# HomemadeHardware_Intro.net
KiCad netlist of a schematic drawn in EAGLE
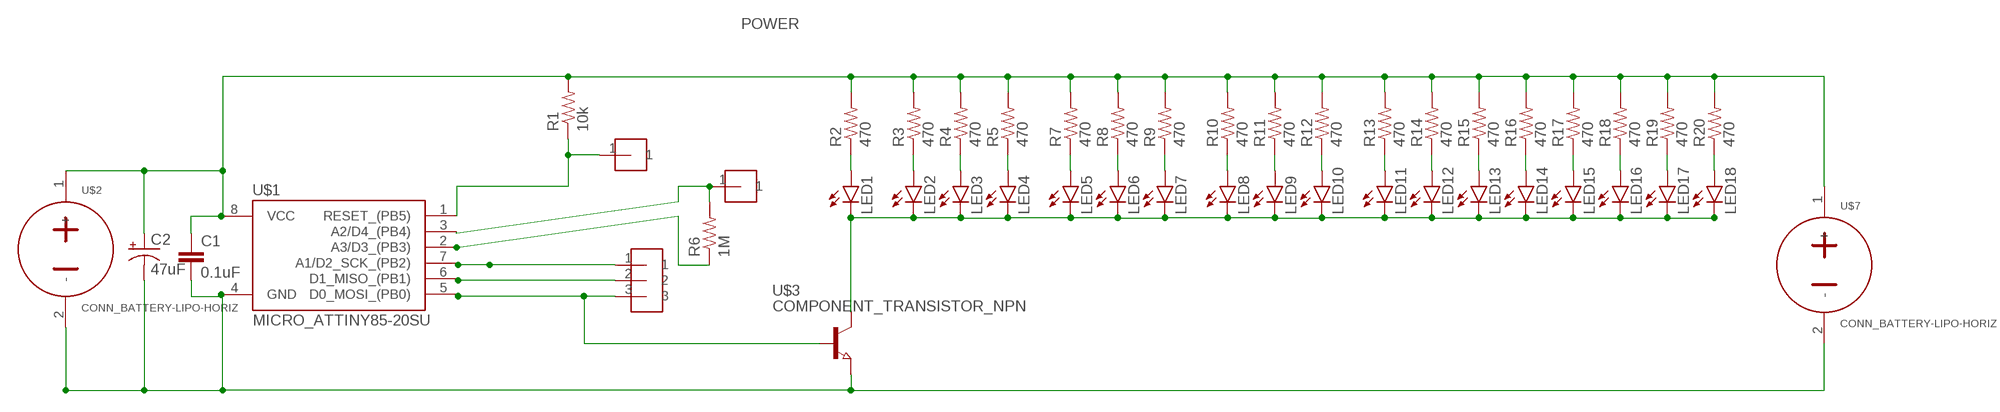
[diagram p0: schematic, sheet 1]

(export (version "E")
  (design (tool "Eeschema 10.0.6"))
  (components
    (comp (ref "C1")
      (value "0.1uF")
      (footprint "eagle-import:0805")
      (libsource (lib "eagle-import") (part "COMPONENT_CAP-0805"))
    )
    (comp (ref "C2")
      (value "47uF")
      (footprint "eagle-import:CAP_RADIAL_CAN_8MM")
      (libsource (lib "eagle-import") (part "COMPONENT_CAP_POL-10MM"))
    )
    (comp (ref "LED1")
      (value "LED-0805")
      (footprint "eagle-import:CHIP-LED0805")
      (libsource (lib "eagle-import") (part "LED-0805"))
    )
    (comp (ref "LED2")
      (value "LED-0805")
      (footprint "eagle-import:CHIP-LED0805")
      (libsource (lib "eagle-import") (part "LED-0805"))
    )
    (comp (ref "LED3")
      (value "LED-0805")
      (footprint "eagle-import:CHIP-LED0805")
      (libsource (lib "eagle-import") (part "LED-0805"))
    )
    (comp (ref "LED4")
      (value "LED-0805")
      (footprint "eagle-import:CHIP-LED0805")
      (libsource (lib "eagle-import") (part "LED-0805"))
    )
    (comp (ref "LED5")
      (value "LED-0805")
      (footprint "eagle-import:CHIP-LED0805")
      (libsource (lib "eagle-import") (part "LED-0805"))
    )
    (comp (ref "LED6")
      (value "LED-0805")
      (footprint "eagle-import:CHIP-LED0805")
      (libsource (lib "eagle-import") (part "LED-0805"))
    )
    (comp (ref "LED7")
      (value "LED-0805")
      (footprint "eagle-import:CHIP-LED0805")
      (libsource (lib "eagle-import") (part "LED-0805"))
    )
    (comp (ref "LED8")
      (value "LED-0805")
      (footprint "eagle-import:CHIP-LED0805")
      (libsource (lib "eagle-import") (part "LED-0805"))
    )
    (comp (ref "LED9")
      (value "LED-0805")
      (footprint "eagle-import:CHIP-LED0805")
      (libsource (lib "eagle-import") (part "LED-0805"))
    )
    (comp (ref "LED10")
      (value "LED-0805")
      (footprint "eagle-import:CHIP-LED0805")
      (libsource (lib "eagle-import") (part "LED-0805"))
    )
    (comp (ref "LED11")
      (value "LED-0805")
      (footprint "eagle-import:CHIP-LED0805")
      (libsource (lib "eagle-import") (part "LED-0805"))
    )
    (comp (ref "LED12")
      (value "LED-0805")
      (footprint "eagle-import:CHIP-LED0805")
      (libsource (lib "eagle-import") (part "LED-0805"))
    )
    (comp (ref "LED13")
      (value "LED-0805")
      (footprint "eagle-import:CHIP-LED0805")
      (libsource (lib "eagle-import") (part "LED-0805"))
    )
    (comp (ref "LED14")
      (value "LED-0805")
      (footprint "eagle-import:CHIP-LED0805")
      (libsource (lib "eagle-import") (part "LED-0805"))
    )
    (comp (ref "LED15")
      (value "LED-0805")
      (footprint "eagle-import:CHIP-LED0805")
      (libsource (lib "eagle-import") (part "LED-0805"))
    )
    (comp (ref "LED16")
      (value "LED-0805")
      (footprint "eagle-import:CHIP-LED0805")
      (libsource (lib "eagle-import") (part "LED-0805"))
    )
    (comp (ref "LED17")
      (value "LED-0805")
      (footprint "eagle-import:CHIP-LED0805")
      (libsource (lib "eagle-import") (part "LED-0805"))
    )
    (comp (ref "LED18")
      (value "LED-0805")
      (footprint "eagle-import:CHIP-LED0805")
      (libsource (lib "eagle-import") (part "LED-0805"))
    )
    (comp (ref "R1")
      (value "10k")
      (footprint "eagle-import:0805")
      (libsource (lib "eagle-import") (part "COMPONENT_RESISTOR-0805"))
    )
    (comp (ref "R2")
      (value "470")
      (footprint "eagle-import:0805")
      (libsource (lib "eagle-import") (part "COMPONENT_RESISTOR-0805"))
    )
    (comp (ref "R3")
      (value "470")
      (footprint "eagle-import:0805")
      (libsource (lib "eagle-import") (part "COMPONENT_RESISTOR-0805"))
    )
    (comp (ref "R4")
      (value "470")
      (footprint "eagle-import:0805")
      (libsource (lib "eagle-import") (part "COMPONENT_RESISTOR-0805"))
    )
    (comp (ref "R5")
      (value "470")
      (footprint "eagle-import:0805")
      (libsource (lib "eagle-import") (part "COMPONENT_RESISTOR-0805"))
    )
    (comp (ref "R6")
      (value "1M")
      (footprint "eagle-import:0805")
      (libsource (lib "eagle-import") (part "COMPONENT_RESISTOR-0805"))
    )
    (comp (ref "R7")
      (value "470")
      (footprint "eagle-import:0805")
      (libsource (lib "eagle-import") (part "COMPONENT_RESISTOR-0805"))
    )
    (comp (ref "R8")
      (value "470")
      (footprint "eagle-import:0805")
      (libsource (lib "eagle-import") (part "COMPONENT_RESISTOR-0805"))
    )
    (comp (ref "R9")
      (value "470")
      (footprint "eagle-import:0805")
      (libsource (lib "eagle-import") (part "COMPONENT_RESISTOR-0805"))
    )
    (comp (ref "R10")
      (value "470")
      (footprint "eagle-import:0805")
      (libsource (lib "eagle-import") (part "COMPONENT_RESISTOR-0805"))
    )
    (comp (ref "R11")
      (value "470")
      (footprint "eagle-import:0805")
      (libsource (lib "eagle-import") (part "COMPONENT_RESISTOR-0805"))
    )
    (comp (ref "R12")
      (value "470")
      (footprint "eagle-import:0805")
      (libsource (lib "eagle-import") (part "COMPONENT_RESISTOR-0805"))
    )
    (comp (ref "R13")
      (value "470")
      (footprint "eagle-import:0805")
      (libsource (lib "eagle-import") (part "COMPONENT_RESISTOR-0805"))
    )
    (comp (ref "R14")
      (value "470")
      (footprint "eagle-import:0805")
      (libsource (lib "eagle-import") (part "COMPONENT_RESISTOR-0805"))
    )
    (comp (ref "R15")
      (value "470")
      (footprint "eagle-import:0805")
      (libsource (lib "eagle-import") (part "COMPONENT_RESISTOR-0805"))
    )
    (comp (ref "R16")
      (value "470")
      (footprint "eagle-import:0805")
      (libsource (lib "eagle-import") (part "COMPONENT_RESISTOR-0805"))
    )
    (comp (ref "R17")
      (value "470")
      (footprint "eagle-import:0805")
      (libsource (lib "eagle-import") (part "COMPONENT_RESISTOR-0805"))
    )
    (comp (ref "R18")
      (value "470")
      (footprint "eagle-import:0805")
      (libsource (lib "eagle-import") (part "COMPONENT_RESISTOR-0805"))
    )
    (comp (ref "R19")
      (value "470")
      (footprint "eagle-import:0805")
      (libsource (lib "eagle-import") (part "COMPONENT_RESISTOR-0805"))
    )
    (comp (ref "R20")
      (value "470")
      (footprint "eagle-import:0805")
      (libsource (lib "eagle-import") (part "COMPONENT_RESISTOR-0805"))
    )
    (comp (ref "U$1")
      (value "MICRO_ATTINY85-20SU")
      (footprint "eagle-import:SOIC8")
      (libsource (lib "eagle-import") (part "MICRO_ATTINY85-20SU"))
    )
    (comp (ref "U$2")
      (value "CONN_BATTERY-LIPO-HORIZ")
      (footprint "eagle-import:JST-PH-2-SMT-RA")
      (libsource (lib "eagle-import") (part "CONN_BATTERY-LIPO-HORIZ"))
    )
    (comp (ref "U$3")
      (value "COMPONENT_TRANSISTOR_NPN")
      (footprint "eagle-import:SOT23")
      (libsource (lib "eagle-import") (part "COMPONENT_TRANSISTOR_NPN"))
    )
    (comp (ref "U$4")
      (value "HEADER-1-TESTPOINT")
      (footprint "eagle-import:TESTPOINT-1")
      (libsource (lib "eagle-import") (part "HEADER-1-TESTPOINT"))
    )
    (comp (ref "U$5")
      (value "HEADER-1-TESTPOINT")
      (footprint "eagle-import:TESTPOINT-1")
      (libsource (lib "eagle-import") (part "HEADER-1-TESTPOINT"))
    )
    (comp (ref "U$6")
      (value "HEADER-3-TESTPOINT")
      (footprint "eagle-import:TESTPOINT-3")
      (libsource (lib "eagle-import") (part "HEADER-3-TESTPOINT"))
    )
    (comp (ref "U$7")
      (value "CONN_BATTERY-LIPO-HORIZ")
      (footprint "eagle-import:JST-PH-2-SMT-RA")
      (libsource (lib "eagle-import") (part "CONN_BATTERY-LIPO-HORIZ"))
    )
  )
  (nets
    (net (code "1") (name "/POWER") (class "Default")
      (node (ref "C1") (pin "1") (pinfunction "1_1") (pintype "passive"))
      (node (ref "C2") (pin "+") (pinfunction "+_+") (pintype "passive"))
      (node (ref "R1") (pin "2") (pinfunction "2_2") (pintype "passive"))
      (node (ref "R10") (pin "2") (pinfunction "2_2") (pintype "passive"))
      (node (ref "R11") (pin "2") (pinfunction "2_2") (pintype "passive"))
      (node (ref "R12") (pin "2") (pinfunction "2_2") (pintype "passive"))
      (node (ref "R13") (pin "2") (pinfunction "2_2") (pintype "passive"))
      (node (ref "R14") (pin "2") (pinfunction "2_2") (pintype "passive"))
      (node (ref "R15") (pin "2") (pinfunction "2_2") (pintype "passive"))
      (node (ref "R16") (pin "2") (pinfunction "2_2") (pintype "passive"))
      (node (ref "R17") (pin "2") (pinfunction "2_2") (pintype "passive"))
      (node (ref "R18") (pin "2") (pinfunction "2_2") (pintype "passive"))
      (node (ref "R19") (pin "2") (pinfunction "2_2") (pintype "passive"))
      (node (ref "R2") (pin "2") (pinfunction "2_2") (pintype "passive"))
      (node (ref "R20") (pin "2") (pinfunction "2_2") (pintype "passive"))
      (node (ref "R3") (pin "2") (pinfunction "2_2") (pintype "passive"))
      (node (ref "R4") (pin "2") (pinfunction "2_2") (pintype "passive"))
      (node (ref "R5") (pin "2") (pinfunction "2_2") (pintype "passive"))
      (node (ref "R7") (pin "2") (pinfunction "2_2") (pintype "passive"))
      (node (ref "R8") (pin "2") (pinfunction "2_2") (pintype "passive"))
      (node (ref "R9") (pin "2") (pinfunction "2_2") (pintype "passive"))
      (node (ref "U$1") (pin "8") (pinfunction "VCC_8") (pintype "power_in"))
      (node (ref "U$2") (pin "1") (pinfunction "+_1") (pintype "bidirectional"))
      (node (ref "U$7") (pin "1") (pinfunction "+_1") (pintype "bidirectional"))
    )
    (net (code "2") (name "Net-(LED1-PadA)") (class "Default")
      (node (ref "LED1") (pin "A") (pinfunction "A_A") (pintype "passive"))
      (node (ref "R2") (pin "1") (pinfunction "1_1") (pintype "passive"))
    )
    (net (code "3") (name "Net-(LED2-PadA)") (class "Default")
      (node (ref "LED2") (pin "A") (pinfunction "A_A") (pintype "passive"))
      (node (ref "R3") (pin "1") (pinfunction "1_1") (pintype "passive"))
    )
    (net (code "4") (name "Net-(LED3-PadA)") (class "Default")
      (node (ref "LED3") (pin "A") (pinfunction "A_A") (pintype "passive"))
      (node (ref "R4") (pin "1") (pinfunction "1_1") (pintype "passive"))
    )
    (net (code "5") (name "Net-(LED4-PadA)") (class "Default")
      (node (ref "LED4") (pin "A") (pinfunction "A_A") (pintype "passive"))
      (node (ref "R5") (pin "1") (pinfunction "1_1") (pintype "passive"))
    )
    (net (code "6") (name "Net-(LED5-PadA)") (class "Default")
      (node (ref "LED5") (pin "A") (pinfunction "A_A") (pintype "passive"))
      (node (ref "R7") (pin "1") (pinfunction "1_1") (pintype "passive"))
    )
    (net (code "7") (name "Net-(LED6-PadA)") (class "Default")
      (node (ref "LED6") (pin "A") (pinfunction "A_A") (pintype "passive"))
      (node (ref "R8") (pin "1") (pinfunction "1_1") (pintype "passive"))
    )
    (net (code "8") (name "Net-(LED7-PadA)") (class "Default")
      (node (ref "LED7") (pin "A") (pinfunction "A_A") (pintype "passive"))
      (node (ref "R9") (pin "1") (pinfunction "1_1") (pintype "passive"))
    )
    (net (code "9") (name "Net-(LED8-PadA)") (class "Default")
      (node (ref "LED8") (pin "A") (pinfunction "A_A") (pintype "passive"))
      (node (ref "R10") (pin "1") (pinfunction "1_1") (pintype "passive"))
    )
    (net (code "10") (name "Net-(LED9-PadA)") (class "Default")
      (node (ref "LED9") (pin "A") (pinfunction "A_A") (pintype "passive"))
      (node (ref "R11") (pin "1") (pinfunction "1_1") (pintype "passive"))
    )
    (net (code "11") (name "Net-(LED10-PadA)") (class "Default")
      (node (ref "LED10") (pin "A") (pinfunction "A_A") (pintype "passive"))
      (node (ref "R12") (pin "1") (pinfunction "1_1") (pintype "passive"))
    )
    (net (code "12") (name "Net-(LED11-PadA)") (class "Default")
      (node (ref "LED11") (pin "A") (pinfunction "A_A") (pintype "passive"))
      (node (ref "R13") (pin "1") (pinfunction "1_1") (pintype "passive"))
    )
    (net (code "13") (name "Net-(LED12-PadA)") (class "Default")
      (node (ref "LED12") (pin "A") (pinfunction "A_A") (pintype "passive"))
      (node (ref "R14") (pin "1") (pinfunction "1_1") (pintype "passive"))
    )
    (net (code "14") (name "Net-(LED13-PadA)") (class "Default")
      (node (ref "LED13") (pin "A") (pinfunction "A_A") (pintype "passive"))
      (node (ref "R15") (pin "1") (pinfunction "1_1") (pintype "passive"))
    )
    (net (code "15") (name "Net-(LED14-PadA)") (class "Default")
      (node (ref "LED14") (pin "A") (pinfunction "A_A") (pintype "passive"))
      (node (ref "R16") (pin "1") (pinfunction "1_1") (pintype "passive"))
    )
    (net (code "16") (name "Net-(LED15-PadA)") (class "Default")
      (node (ref "LED15") (pin "A") (pinfunction "A_A") (pintype "passive"))
      (node (ref "R17") (pin "1") (pinfunction "1_1") (pintype "passive"))
    )
    (net (code "17") (name "Net-(LED16-PadA)") (class "Default")
      (node (ref "LED16") (pin "A") (pinfunction "A_A") (pintype "passive"))
      (node (ref "R18") (pin "1") (pinfunction "1_1") (pintype "passive"))
    )
    (net (code "18") (name "Net-(LED17-PadA)") (class "Default")
      (node (ref "LED17") (pin "A") (pinfunction "A_A") (pintype "passive"))
      (node (ref "R19") (pin "1") (pinfunction "1_1") (pintype "passive"))
    )
    (net (code "19") (name "Net-(LED18-PadA)") (class "Default")
      (node (ref "LED18") (pin "A") (pinfunction "A_A") (pintype "passive"))
      (node (ref "R20") (pin "1") (pinfunction "1_1") (pintype "passive"))
    )
    (net (code "20") (name "Net-(U$1-A1{slash}D2_SCK_(PB2))") (class "Default")
      (node (ref "U$1") (pin "7") (pinfunction "A1/D2_SCK_(PB2)_7") (pintype "bidirectional"))
      (node (ref "U$6") (pin "1") (pinfunction "1_1") (pintype "bidirectional"))
    )
    (net (code "21") (name "Net-(U$1-A2{slash}D4_(PB4))") (class "Default")
      (node (ref "R6") (pin "2") (pinfunction "2_2") (pintype "passive"))
      (node (ref "U$1") (pin "3") (pinfunction "A2/D4_(PB4)_3") (pintype "bidirectional"))
      (node (ref "U$4") (pin "1") (pinfunction "1_1") (pintype "bidirectional"))
    )
    (net (code "22") (name "Net-(U$1-A3{slash}D3_(PB3))") (class "Default")
      (node (ref "R6") (pin "1") (pinfunction "1_1") (pintype "passive"))
      (node (ref "U$1") (pin "2") (pinfunction "A3/D3_(PB3)_2") (pintype "bidirectional"))
    )
    (net (code "23") (name "Net-(U$1-D0_MOSI_(PB0))") (class "Default")
      (node (ref "U$1") (pin "5") (pinfunction "D0_MOSI_(PB0)_5") (pintype "bidirectional"))
      (node (ref "U$3") (pin "1") (pinfunction "B_1") (pintype "passive"))
      (node (ref "U$6") (pin "3") (pinfunction "3_3") (pintype "bidirectional"))
    )
    (net (code "24") (name "Net-(U$1-D1_MISO_(PB1))") (class "Default")
      (node (ref "U$1") (pin "6") (pinfunction "D1_MISO_(PB1)_6") (pintype "bidirectional"))
      (node (ref "U$6") (pin "2") (pinfunction "2_2") (pintype "bidirectional"))
    )
    (net (code "25") (name "Net-(U$1-GND)") (class "Default")
      (node (ref "C1") (pin "2") (pinfunction "2_2") (pintype "passive"))
      (node (ref "C2") (pin "-") (pinfunction "-_-") (pintype "passive"))
      (node (ref "U$1") (pin "4") (pinfunction "GND_4") (pintype "power_in"))
      (node (ref "U$2") (pin "2") (pinfunction "-_2") (pintype "bidirectional"))
      (node (ref "U$3") (pin "2") (pinfunction "E_2") (pintype "passive"))
      (node (ref "U$7") (pin "2") (pinfunction "-_2") (pintype "bidirectional"))
    )
    (net (code "26") (name "Net-(U$1-RESET_(PB5))") (class "Default")
      (node (ref "R1") (pin "1") (pinfunction "1_1") (pintype "passive"))
      (node (ref "U$1") (pin "1") (pinfunction "RESET_(PB5)_1") (pintype "bidirectional"))
      (node (ref "U$5") (pin "1") (pinfunction "1_1") (pintype "bidirectional"))
    )
    (net (code "27") (name "Net-(U$3-C)") (class "Default")
      (node (ref "LED1") (pin "C") (pinfunction "C_C") (pintype "passive"))
      (node (ref "LED10") (pin "C") (pinfunction "C_C") (pintype "passive"))
      (node (ref "LED11") (pin "C") (pinfunction "C_C") (pintype "passive"))
      (node (ref "LED12") (pin "C") (pinfunction "C_C") (pintype "passive"))
      (node (ref "LED13") (pin "C") (pinfunction "C_C") (pintype "passive"))
      (node (ref "LED14") (pin "C") (pinfunction "C_C") (pintype "passive"))
      (node (ref "LED15") (pin "C") (pinfunction "C_C") (pintype "passive"))
      (node (ref "LED16") (pin "C") (pinfunction "C_C") (pintype "passive"))
      (node (ref "LED17") (pin "C") (pinfunction "C_C") (pintype "passive"))
      (node (ref "LED18") (pin "C") (pinfunction "C_C") (pintype "passive"))
      (node (ref "LED2") (pin "C") (pinfunction "C_C") (pintype "passive"))
      (node (ref "LED3") (pin "C") (pinfunction "C_C") (pintype "passive"))
      (node (ref "LED4") (pin "C") (pinfunction "C_C") (pintype "passive"))
      (node (ref "LED5") (pin "C") (pinfunction "C_C") (pintype "passive"))
      (node (ref "LED6") (pin "C") (pinfunction "C_C") (pintype "passive"))
      (node (ref "LED7") (pin "C") (pinfunction "C_C") (pintype "passive"))
      (node (ref "LED8") (pin "C") (pinfunction "C_C") (pintype "passive"))
      (node (ref "LED9") (pin "C") (pinfunction "C_C") (pintype "passive"))
      (node (ref "U$3") (pin "3") (pinfunction "C_3") (pintype "passive"))
    )
  )
)
